# lm75_eeprom.net
KiCad netlist of a schematic drawn in Altium Designer
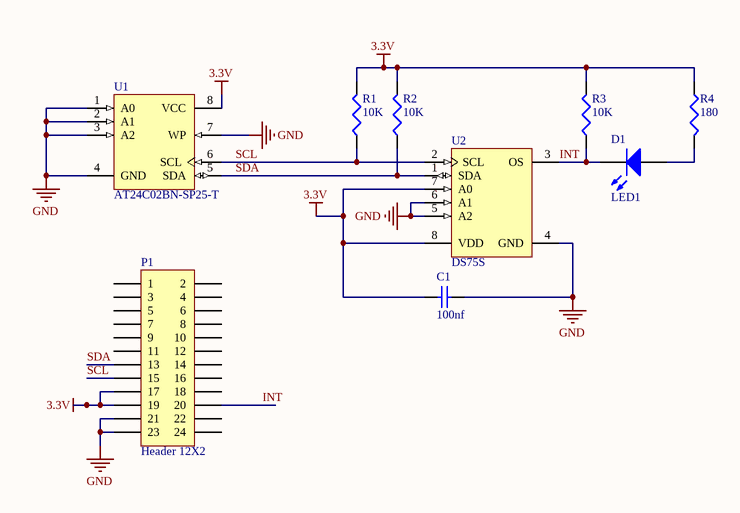
[diagram p0: lm75&eeprom.SchDoc]

(export (version "E")
  (design (tool "Eeschema 10.0.6"))
  (components
    (comp (ref "C1")
      (value "100nf")
      (footprint "C1206")
      (description "Capacitor (Semiconductor SIM Model)")
      (fields (field (name "PUBLISHER") "Altium Limited"))
      (libsource (lib "Miscellaneous Devices") (part "Cap Semi"))
    )
    (comp (ref "D1")
      (value "LED1")
      (footprint "3.5X2.8X1.9")
      (description "Typical BLUE SiC LED")
      (fields (field (name "PUBLISHER") "Altium Limited"))
      (libsource (lib "Miscellaneous Devices") (part "LED3"))
    )
    (comp (ref "P1")
      (value "Header 12X2")
      (footprint "HDR2X12")
      (description "Header, 12-Pin, Dual row")
      (fields (field (name "PUBLISHER") "Altium Limited"))
      (libsource (lib "Miscellaneous Connectors") (part "Header 12X2"))
    )
    (comp (ref "R1")
      (value "10K")
      (footprint "1206")
      (description "Resistor")
      (fields (field (name "PUBLISHER") "Altium Limited"))
      (libsource (lib "Miscellaneous Devices") (part "Res3"))
    )
    (comp (ref "R2")
      (value "10K")
      (footprint "1206")
      (description "Resistor")
      (fields (field (name "PUBLISHER") "Altium Limited"))
      (libsource (lib "Miscellaneous Devices") (part "Res3"))
    )
    (comp (ref "R3")
      (value "10K")
      (footprint "1206")
      (description "Resistor")
      (fields (field (name "PUBLISHER") "Altium Limited"))
      (libsource (lib "Miscellaneous Devices") (part "Res3"))
    )
    (comp (ref "R4")
      (value "180")
      (footprint "1206")
      (description "Resistor")
      (fields (field (name "PUBLISHER") "Altium Limited"))
      (libsource (lib "Miscellaneous Devices") (part "Res3"))
    )
    (comp (ref "U1")
      (value "AT24C02BN-SP25-T")
      (footprint "8S1_N")
      (libsource (lib "Atmel Serial EEPROM") (part "AT24C02BN-SP25-T"))
    )
    (comp (ref "U2")
      (value "DS75S")
      (footprint "MAXM-S8-2_N")
      (fields (field (name "GENERIC PART NUMBER") "DS75"))
      (libsource (lib "Maxim Sensors") (part "DS75S"))
    )
  )
  (nets
    (net (code "1") (name "/INT") (class "Default")
      (node (ref "D1") (pin "2") (pinfunction "K_2") (pintype "passive"))
      (node (ref "P1") (pin "20") (pinfunction "20_20") (pintype "passive"))
      (node (ref "R3") (pin "1") (pinfunction "1_1") (pintype "passive"))
      (node (ref "U2") (pin "3") (pinfunction "OS_3") (pintype "open_collector"))
    )
    (net (code "2") (name "/SCL") (class "Default")
      (node (ref "P1") (pin "15") (pinfunction "15_15") (pintype "passive"))
      (node (ref "R1") (pin "1") (pinfunction "1_1") (pintype "passive"))
      (node (ref "U1") (pin "6") (pinfunction "SCL_6") (pintype "input"))
      (node (ref "U2") (pin "2") (pinfunction "SCL_2") (pintype "input"))
    )
    (net (code "3") (name "/SDA") (class "Default")
      (node (ref "P1") (pin "13") (pinfunction "13_13") (pintype "passive"))
      (node (ref "R2") (pin "1") (pinfunction "1_1") (pintype "passive"))
      (node (ref "U1") (pin "5") (pinfunction "SDA_5") (pintype "bidirectional"))
      (node (ref "U2") (pin "1") (pinfunction "SDA_1") (pintype "bidirectional"))
    )
    (net (code "4") (name "3.3V") (class "Default")
      (node (ref "C1") (pin "1") (pinfunction "1_1") (pintype "passive"))
      (node (ref "P1") (pin "17") (pinfunction "17_17") (pintype "passive"))
      (node (ref "P1") (pin "19") (pinfunction "19_19") (pintype "passive"))
      (node (ref "R1") (pin "2") (pinfunction "2_2") (pintype "passive"))
      (node (ref "R2") (pin "2") (pinfunction "2_2") (pintype "passive"))
      (node (ref "R3") (pin "2") (pinfunction "2_2") (pintype "passive"))
      (node (ref "R4") (pin "1") (pinfunction "1_1") (pintype "passive"))
      (node (ref "U1") (pin "8") (pinfunction "VCC_8") (pintype "power_in"))
      (node (ref "U2") (pin "7") (pinfunction "A0_7") (pintype "input"))
      (node (ref "U2") (pin "8") (pinfunction "VDD_8") (pintype "power_in"))
    )
    (net (code "5") (name "GND") (class "Default")
      (node (ref "C1") (pin "2") (pinfunction "2_2") (pintype "passive"))
      (node (ref "P1") (pin "21") (pinfunction "21_21") (pintype "passive"))
      (node (ref "P1") (pin "23") (pinfunction "23_23") (pintype "passive"))
      (node (ref "U1") (pin "1") (pinfunction "A0_1") (pintype "input"))
      (node (ref "U1") (pin "2") (pinfunction "A1_2") (pintype "input"))
      (node (ref "U1") (pin "3") (pinfunction "A2_3") (pintype "input"))
      (node (ref "U1") (pin "4") (pinfunction "GND_4") (pintype "power_in"))
      (node (ref "U1") (pin "7") (pinfunction "WP_7") (pintype "input"))
      (node (ref "U2") (pin "4") (pinfunction "GND_4") (pintype "power_in"))
      (node (ref "U2") (pin "5") (pinfunction "A2_5") (pintype "input"))
      (node (ref "U2") (pin "6") (pinfunction "A1_6") (pintype "input"))
    )
    (net (code "6") (name "Net-(D1-A)") (class "Default")
      (node (ref "D1") (pin "1") (pinfunction "A_1") (pintype "passive"))
      (node (ref "R4") (pin "2") (pinfunction "2_2") (pintype "passive"))
    )
    (net (code "7") (name "unconnected-(P1-Pad1)") (class "Default")
      (node (ref "P1") (pin "1") (pinfunction "1_1") (pintype "passive"))
    )
    (net (code "8") (name "unconnected-(P1-Pad2)") (class "Default")
      (node (ref "P1") (pin "2") (pinfunction "2_2") (pintype "passive"))
    )
    (net (code "9") (name "unconnected-(P1-Pad3)") (class "Default")
      (node (ref "P1") (pin "3") (pinfunction "3_3") (pintype "passive"))
    )
    (net (code "10") (name "unconnected-(P1-Pad4)") (class "Default")
      (node (ref "P1") (pin "4") (pinfunction "4_4") (pintype "passive"))
    )
    (net (code "11") (name "unconnected-(P1-Pad5)") (class "Default")
      (node (ref "P1") (pin "5") (pinfunction "5_5") (pintype "passive"))
    )
    (net (code "12") (name "unconnected-(P1-Pad6)") (class "Default")
      (node (ref "P1") (pin "6") (pinfunction "6_6") (pintype "passive"))
    )
    (net (code "13") (name "unconnected-(P1-Pad7)") (class "Default")
      (node (ref "P1") (pin "7") (pinfunction "7_7") (pintype "passive"))
    )
    (net (code "14") (name "unconnected-(P1-Pad8)") (class "Default")
      (node (ref "P1") (pin "8") (pinfunction "8_8") (pintype "passive"))
    )
    (net (code "15") (name "unconnected-(P1-Pad9)") (class "Default")
      (node (ref "P1") (pin "9") (pinfunction "9_9") (pintype "passive"))
    )
    (net (code "16") (name "unconnected-(P1-Pad10)") (class "Default")
      (node (ref "P1") (pin "10") (pinfunction "10_10") (pintype "passive"))
    )
    (net (code "17") (name "unconnected-(P1-Pad11)") (class "Default")
      (node (ref "P1") (pin "11") (pinfunction "11_11") (pintype "passive"))
    )
    (net (code "18") (name "unconnected-(P1-Pad12)") (class "Default")
      (node (ref "P1") (pin "12") (pinfunction "12_12") (pintype "passive"))
    )
    (net (code "19") (name "unconnected-(P1-Pad14)") (class "Default")
      (node (ref "P1") (pin "14") (pinfunction "14_14") (pintype "passive"))
    )
    (net (code "20") (name "unconnected-(P1-Pad16)") (class "Default")
      (node (ref "P1") (pin "16") (pinfunction "16_16") (pintype "passive"))
    )
    (net (code "21") (name "unconnected-(P1-Pad18)") (class "Default")
      (node (ref "P1") (pin "18") (pinfunction "18_18") (pintype "passive"))
    )
    (net (code "22") (name "unconnected-(P1-Pad22)") (class "Default")
      (node (ref "P1") (pin "22") (pinfunction "22_22") (pintype "passive"))
    )
    (net (code "23") (name "unconnected-(P1-Pad24)") (class "Default")
      (node (ref "P1") (pin "24") (pinfunction "24_24") (pintype "passive"))
    )
  )
)
